# EVB-ANNA-B5_SCHEM_0003_USBhub_FTDI.net
KiCad netlist of a schematic drawn in Altium Designer
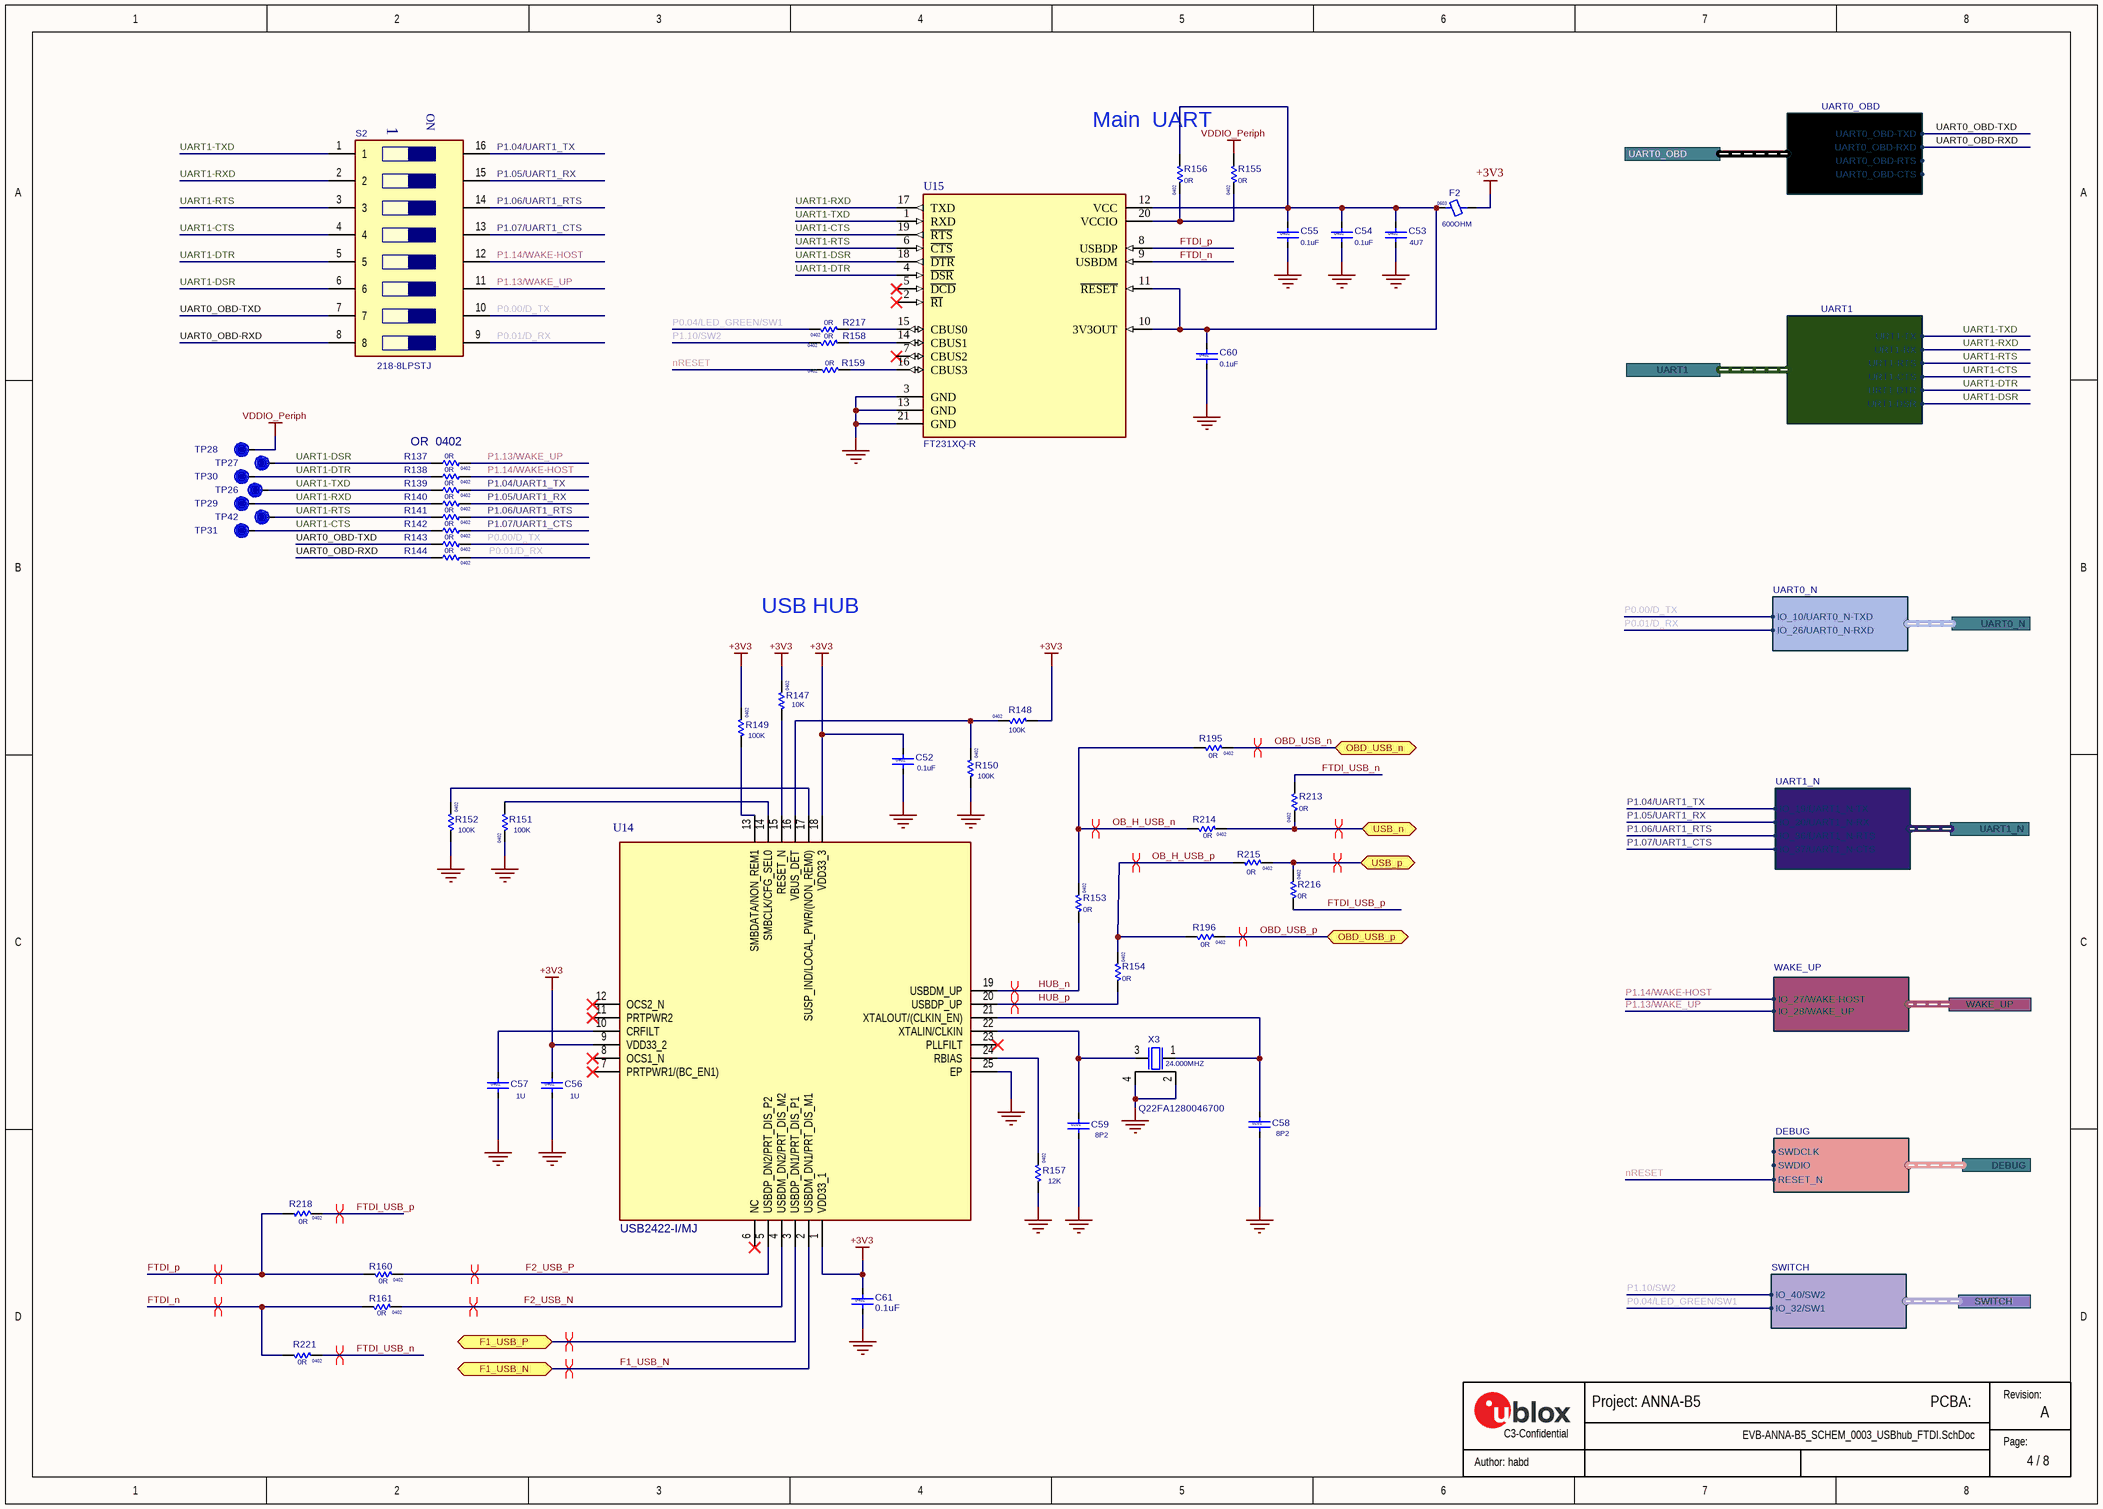
[diagram p0: EVB-ANNA-B5_SCHEM_0003_USBhub_FTDI.SchDoc]

(export (version "E")
  (design (tool "Eeschema 10.0.6"))
  (components
    (comp (ref "C52")
      (value "0.1uF")
      (footprint "Cap 0402 HD")
      (description "Cap, Ceramic 0.1uF 10V 10% X5R 0402")
      (fields
        (field (name "SIZE") "0402")
        (field (name "PART NUMBER") "120-00016")
        (field (name "MANUFACTURER") "Murata Electronics North America")
      )
      (libsource (lib "Arena_Parts_DB_Lib") (part "Cap Chip"))
    )
    (comp (ref "C53")
      (value "4U7")
      (footprint "Cap 0402 HD")
      (description "CAP CER X5R 0402 4U7 20% 10V")
      (fields
        (field (name "SIZE") "0402")
        (field (name "PART NUMBER") "UBXH01-0000243")
        (field (name "TOLERANCE") "20%")
        (field (name "EDITOR") "martin.pilik")
        (field (name "RELEASED BY") "fabrice.bret-dibat")
      )
      (libsource (lib "UBX_Parts_DB_Lib") (part "Cap Chip"))
    )
    (comp (ref "C54")
      (value "0.1uF")
      (footprint "Cap 0402 HD")
      (description "Cap, Ceramic 0.1uF 10V 10% X5R 0402")
      (fields
        (field (name "SIZE") "0402")
        (field (name "PART NUMBER") "120-00016")
        (field (name "MANUFACTURER") "Murata Electronics North America")
      )
      (libsource (lib "Arena_Parts_DB_Lib") (part "Cap Chip"))
    )
    (comp (ref "C55")
      (value "0.1uF")
      (footprint "Cap 0402 HD")
      (description "Cap, Ceramic 0.1uF 10V 10% X5R 0402")
      (fields
        (field (name "SIZE") "0402")
        (field (name "PART NUMBER") "120-00016")
        (field (name "MANUFACTURER") "Murata Electronics North America")
      )
      (libsource (lib "Arena_Parts_DB_Lib") (part "Cap Chip"))
    )
    (comp (ref "C56")
      (value "1U")
      (footprint "Cap 0402 HD")
      (description "CAP CER X5R 0402 1U 10% 10V")
      (fields
        (field (name "SIZE") "0402")
        (field (name "PART NUMBER") "UBXH01-0000248")
        (field (name "TOLERANCE") "10%")
        (field (name "EDITOR") "michael.hein")
        (field (name "RELEASED BY") "igor.shevchenko")
      )
      (libsource (lib "UBX_Parts_DB_Lib") (part "Cap Chip"))
    )
    (comp (ref "C57")
      (value "1U")
      (footprint "Cap 0402 HD")
      (description "CAP CER X5R 0402 1U 10% 10V")
      (fields
        (field (name "SIZE") "0402")
        (field (name "PART NUMBER") "UBXH01-0000248")
        (field (name "TOLERANCE") "10%")
        (field (name "EDITOR") "michael.hein")
        (field (name "RELEASED BY") "igor.shevchenko")
      )
      (libsource (lib "UBX_Parts_DB_Lib") (part "Cap Chip"))
    )
    (comp (ref "C58")
      (value "8P2")
      (footprint "Cap 0201 HD")
      (description "CAP CER C0G 0201 8P2 +/-0.5P 25V")
      (fields
        (field (name "SIZE") "0201")
        (field (name "PART NUMBER") "UBXH01-0013002")
        (field (name "TOLERANCE") "+/-0.5P")
        (field (name "EDITOR") "roland.rust")
        (field (name "RELEASED BY") "roland.rust")
      )
      (libsource (lib "UBX_Parts_DB_Lib") (part "Cap Chip"))
    )
    (comp (ref "C59")
      (value "8P2")
      (footprint "Cap 0201 HD")
      (description "CAP CER C0G 0201 8P2 +/-0.5P 25V")
      (fields
        (field (name "SIZE") "0201")
        (field (name "PART NUMBER") "UBXH01-0013002")
        (field (name "TOLERANCE") "+/-0.5P")
        (field (name "EDITOR") "roland.rust")
        (field (name "RELEASED BY") "roland.rust")
      )
      (libsource (lib "UBX_Parts_DB_Lib") (part "Cap Chip"))
    )
    (comp (ref "C60")
      (value "0.1uF")
      (footprint "Cap 0402 HD")
      (description "Cap, Ceramic 0.1uF 10V 10% X5R 0402")
      (fields
        (field (name "SIZE") "0402")
        (field (name "PART NUMBER") "120-00016")
        (field (name "MANUFACTURER") "Murata Electronics North America")
      )
      (libsource (lib "Arena_Parts_DB_Lib") (part "Cap Chip"))
    )
    (comp (ref "C61")
      (value "0.1uF")
      (footprint "Cap 0402 HD")
      (description "Cap, Ceramic 0.1uF 10V 10% X5R 0402")
      (fields
        (field (name "SIZE") "0402")
        (field (name "PART NUMBER") "120-00016")
        (field (name "MANUFACTURER") "Murata Electronics North America")
      )
      (libsource (lib "Arena_Parts_DB_Lib") (part "Cap Chip"))
    )
    (comp (ref "F2")
      (value "600OHM")
      (footprint "IND_0603_1750Lx950Wx1050H_600x800Pad_800G_FLX")
      (description "FERRITE BEAD 0603 600 OHM AT 100MHZ 600OHM 500mA")
      (fields
        (field (name "SIZE") "0603")
        (field (name "PART NUMBER") "UBXH08-0000001")
        (field (name "MANUFACTURER") "TDK Corporation")
        (field (name "EDITOR") "daniel.hurni")
        (field (name "RELEASED BY") "martin.frauchiger")
      )
      (libsource (lib "UBX_Parts_DB_Lib") (part "FB sm"))
    )
    (comp (ref "R137")
      (value "0R")
      (footprint "RES 0402 HD")
      (description "RES THICK FILM CHIP 0402 0R 0 100mW")
      (fields
        (field (name "SIZE") "0402")
        (field (name "PART NUMBER") "UBXH18-0003002")
        (field (name "TOLERANCE") "0")
        (field (name "EDITOR") "charlotte.biber")
        (field (name "RELEASED BY") "peter.mueller")
      )
      (libsource (lib "UBX_Parts_DB_Lib") (part "Res sm"))
    )
    (comp (ref "R138")
      (value "0R")
      (footprint "RES 0402 HD")
      (description "RES THICK FILM CHIP 0402 0R 0 100mW")
      (fields
        (field (name "SIZE") "0402")
        (field (name "PART NUMBER") "UBXH18-0003002")
        (field (name "TOLERANCE") "0")
        (field (name "EDITOR") "charlotte.biber")
        (field (name "RELEASED BY") "peter.mueller")
      )
      (libsource (lib "UBX_Parts_DB_Lib") (part "Res sm"))
    )
    (comp (ref "R139")
      (value "0R")
      (footprint "RES 0402 HD")
      (description "RES THICK FILM CHIP 0402 0R 0 100mW")
      (fields
        (field (name "SIZE") "0402")
        (field (name "PART NUMBER") "UBXH18-0003002")
        (field (name "TOLERANCE") "0")
        (field (name "EDITOR") "charlotte.biber")
        (field (name "RELEASED BY") "peter.mueller")
      )
      (libsource (lib "UBX_Parts_DB_Lib") (part "Res sm"))
    )
    (comp (ref "R140")
      (value "0R")
      (footprint "RES 0402 HD")
      (description "RES THICK FILM CHIP 0402 0R 0 100mW")
      (fields
        (field (name "SIZE") "0402")
        (field (name "PART NUMBER") "UBXH18-0003002")
        (field (name "TOLERANCE") "0")
        (field (name "EDITOR") "charlotte.biber")
        (field (name "RELEASED BY") "peter.mueller")
      )
      (libsource (lib "UBX_Parts_DB_Lib") (part "Res sm"))
    )
    (comp (ref "R141")
      (value "0R")
      (footprint "RES 0402 HD")
      (description "RES THICK FILM CHIP 0402 0R 0 100mW")
      (fields
        (field (name "SIZE") "0402")
        (field (name "PART NUMBER") "UBXH18-0003002")
        (field (name "TOLERANCE") "0")
        (field (name "EDITOR") "charlotte.biber")
        (field (name "RELEASED BY") "peter.mueller")
      )
      (libsource (lib "UBX_Parts_DB_Lib") (part "Res sm"))
    )
    (comp (ref "R142")
      (value "0R")
      (footprint "RES 0402 HD")
      (description "RES THICK FILM CHIP 0402 0R 0 100mW")
      (fields
        (field (name "SIZE") "0402")
        (field (name "PART NUMBER") "UBXH18-0003002")
        (field (name "TOLERANCE") "0")
        (field (name "EDITOR") "charlotte.biber")
        (field (name "RELEASED BY") "peter.mueller")
      )
      (libsource (lib "UBX_Parts_DB_Lib") (part "Res sm"))
    )
    (comp (ref "R143")
      (value "0R")
      (footprint "RES 0402 HD")
      (description "RES THICK FILM CHIP 0402 0R 0 100mW")
      (fields
        (field (name "SIZE") "0402")
        (field (name "PART NUMBER") "UBXH18-0003002")
        (field (name "TOLERANCE") "0")
        (field (name "EDITOR") "charlotte.biber")
        (field (name "RELEASED BY") "peter.mueller")
      )
      (libsource (lib "UBX_Parts_DB_Lib") (part "Res sm"))
    )
    (comp (ref "R144")
      (value "0R")
      (footprint "RES 0402 HD")
      (description "RES THICK FILM CHIP 0402 0R 0 100mW")
      (fields
        (field (name "SIZE") "0402")
        (field (name "PART NUMBER") "UBXH18-0003002")
        (field (name "TOLERANCE") "0")
        (field (name "EDITOR") "charlotte.biber")
        (field (name "RELEASED BY") "peter.mueller")
      )
      (libsource (lib "UBX_Parts_DB_Lib") (part "Res sm"))
    )
    (comp (ref "R147")
      (value "10K")
      (footprint "RES 0402 HD")
      (description "RES THICK FILM CHIP 0402 10K 1% 63mW")
      (fields
        (field (name "SIZE") "0402")
        (field (name "PART NUMBER") "UBXH18-0000065")
        (field (name "TOLERANCE") "1%")
        (field (name "EDITOR") "erian.bezhani")
        (field (name "RELEASED BY") "massimo.vlacci")
      )
      (libsource (lib "UBX_Parts_DB_Lib") (part "Res sm"))
    )
    (comp (ref "R148")
      (value "100K")
      (footprint "RES 0402 HD")
      (description "RES THICK FILM CHIP 0402 100K 1% 63mW")
      (fields
        (field (name "SIZE") "0402")
        (field (name "PART NUMBER") "UBXH18-0000005")
        (field (name "TOLERANCE") "1%")
        (field (name "EDITOR") "dario.antonaz")
        (field (name "RELEASED BY") "sandro.sestan")
      )
      (libsource (lib "UBX_Parts_DB_Lib") (part "Res sm"))
    )
    (comp (ref "R149")
      (value "100K")
      (footprint "RES 0402 HD")
      (description "RES THICK FILM CHIP 0402 100K 1% 63mW")
      (fields
        (field (name "SIZE") "0402")
        (field (name "PART NUMBER") "UBXH18-0000005")
        (field (name "TOLERANCE") "1%")
        (field (name "EDITOR") "dario.antonaz")
        (field (name "RELEASED BY") "sandro.sestan")
      )
      (libsource (lib "UBX_Parts_DB_Lib") (part "Res sm"))
    )
    (comp (ref "R150")
      (value "100K")
      (footprint "RES 0402 HD")
      (description "RES THICK FILM CHIP 0402 100K 1% 63mW")
      (fields
        (field (name "SIZE") "0402")
        (field (name "PART NUMBER") "UBXH18-0000005")
        (field (name "TOLERANCE") "1%")
        (field (name "EDITOR") "dario.antonaz")
        (field (name "RELEASED BY") "sandro.sestan")
      )
      (libsource (lib "UBX_Parts_DB_Lib") (part "Res sm"))
    )
    (comp (ref "R151")
      (value "100K")
      (footprint "RES 0402 HD")
      (description "RES THICK FILM CHIP 0402 100K 1% 63mW")
      (fields
        (field (name "SIZE") "0402")
        (field (name "PART NUMBER") "UBXH18-0000005")
        (field (name "TOLERANCE") "1%")
        (field (name "EDITOR") "dario.antonaz")
        (field (name "RELEASED BY") "sandro.sestan")
      )
      (libsource (lib "UBX_Parts_DB_Lib") (part "Res sm"))
    )
    (comp (ref "R152")
      (value "100K")
      (footprint "RES 0402 HD")
      (description "RES THICK FILM CHIP 0402 100K 1% 63mW")
      (fields
        (field (name "SIZE") "0402")
        (field (name "PART NUMBER") "UBXH18-0000005")
        (field (name "TOLERANCE") "1%")
        (field (name "EDITOR") "dario.antonaz")
        (field (name "RELEASED BY") "sandro.sestan")
      )
      (libsource (lib "UBX_Parts_DB_Lib") (part "Res sm"))
    )
    (comp (ref "R153")
      (value "0R")
      (footprint "RES 0402 HD")
      (description "RES THICK FILM CHIP 0402 0R 0 100mW")
      (fields
        (field (name "SIZE") "0402")
        (field (name "PART NUMBER") "UBXH18-0003002")
        (field (name "TOLERANCE") "0")
        (field (name "EDITOR") "charlotte.biber")
        (field (name "RELEASED BY") "peter.mueller")
      )
      (libsource (lib "UBX_Parts_DB_Lib") (part "Res sm"))
    )
    (comp (ref "R154")
      (value "0R")
      (footprint "RES 0402 HD")
      (description "RES THICK FILM CHIP 0402 0R 0 100mW")
      (fields
        (field (name "SIZE") "0402")
        (field (name "PART NUMBER") "UBXH18-0003002")
        (field (name "TOLERANCE") "0")
        (field (name "EDITOR") "charlotte.biber")
        (field (name "RELEASED BY") "peter.mueller")
      )
      (libsource (lib "UBX_Parts_DB_Lib") (part "Res sm"))
    )
    (comp (ref "R155")
      (value "0R")
      (footprint "RES 0402 HD")
      (description "RES THICK FILM CHIP 0402 0R 0 100mW")
      (fields
        (field (name "SIZE") "0402")
        (field (name "PART NUMBER") "UBXH18-0003002")
        (field (name "TOLERANCE") "0")
        (field (name "EDITOR") "charlotte.biber")
        (field (name "RELEASED BY") "peter.mueller")
      )
      (libsource (lib "UBX_Parts_DB_Lib") (part "Res sm"))
    )
    (comp (ref "R156")
      (value "0R")
      (footprint "RES 0402 HD")
      (description "RES THICK FILM CHIP 0402 0R 0 100mW")
      (fields
        (field (name "SIZE") "0402")
        (field (name "PART NUMBER") "UBXH18-0003002")
        (field (name "TOLERANCE") "0")
        (field (name "EDITOR") "charlotte.biber")
        (field (name "RELEASED BY") "peter.mueller")
      )
      (libsource (lib "UBX_Parts_DB_Lib") (part "Res sm"))
    )
    (comp (ref "R157")
      (value "12K")
      (footprint "RES_0402_1100Lx600Wx400H_500x600Pad_400G_FLX")
      (description "RES THICK FILM CHIP 0402 12K 1% 62.5mW")
      (fields
        (field (name "SIZE") "0402")
        (field (name "PART NUMBER") "UBXH18-0000133")
        (field (name "TOLERANCE") "1%")
        (field (name "EDITOR") "pierpaolo.arban")
        (field (name "RELEASED BY") "dario.antonaz")
      )
      (libsource (lib "UBX_Parts_DB_Lib") (part "Res sm"))
    )
    (comp (ref "R158")
      (value "0R")
      (footprint "RES_0402_1100Lx600Wx400H_500x600Pad_400G_FLX")
      (description "RES THICK FILM CHIP 0402 0R 0 100mW")
      (fields
        (field (name "SIZE") "0402")
        (field (name "PART NUMBER") "UBXH18-0003002")
        (field (name "TOLERANCE") "0")
        (field (name "EDITOR") "charlotte.biber")
        (field (name "RELEASED BY") "peter.mueller")
      )
      (libsource (lib "UBX_Parts_DB_Lib") (part "Res sm"))
    )
    (comp (ref "R159")
      (value "0R")
      (footprint "RES_0402_1100Lx600Wx400H_500x600Pad_400G_FLX")
      (description "RES THICK FILM CHIP 0402 0R 0 100mW")
      (fields
        (field (name "SIZE") "0402")
        (field (name "PART NUMBER") "UBXH18-0003002")
        (field (name "TOLERANCE") "0")
        (field (name "EDITOR") "charlotte.biber")
        (field (name "RELEASED BY") "peter.mueller")
      )
      (libsource (lib "UBX_Parts_DB_Lib") (part "Res sm"))
    )
    (comp (ref "R160")
      (value "0R")
      (footprint "RES 0402 HD")
      (description "RES THICK FILM CHIP 0402 0R 0 100mW")
      (fields
        (field (name "SIZE") "0402")
        (field (name "PART NUMBER") "UBXH18-0003002")
        (field (name "TOLERANCE") "0")
        (field (name "EDITOR") "charlotte.biber")
        (field (name "RELEASED BY") "peter.mueller")
      )
      (libsource (lib "UBX_Parts_DB_Lib") (part "Res sm"))
    )
    (comp (ref "R161")
      (value "0R")
      (footprint "RES 0402 HD")
      (description "RES THICK FILM CHIP 0402 0R 0 100mW")
      (fields
        (field (name "SIZE") "0402")
        (field (name "PART NUMBER") "UBXH18-0003002")
        (field (name "TOLERANCE") "0")
        (field (name "EDITOR") "charlotte.biber")
        (field (name "RELEASED BY") "peter.mueller")
      )
      (libsource (lib "UBX_Parts_DB_Lib") (part "Res sm"))
    )
    (comp (ref "R195")
      (value "0R")
      (footprint "RES 0402 HD")
      (description "RES THICK FILM CHIP 0402 0R 0 100mW")
      (fields
        (field (name "SIZE") "0402")
        (field (name "PART NUMBER") "UBXH18-0003002")
        (field (name "TOLERANCE") "0")
        (field (name "EDITOR") "charlotte.biber")
        (field (name "RELEASED BY") "peter.mueller")
      )
      (libsource (lib "UBX_Parts_DB_Lib") (part "Res sm"))
    )
    (comp (ref "R196")
      (value "0R")
      (footprint "RES 0402 HD")
      (description "RES THICK FILM CHIP 0402 0R 0 100mW")
      (fields
        (field (name "SIZE") "0402")
        (field (name "PART NUMBER") "UBXH18-0003002")
        (field (name "TOLERANCE") "0")
        (field (name "EDITOR") "charlotte.biber")
        (field (name "RELEASED BY") "peter.mueller")
      )
      (libsource (lib "UBX_Parts_DB_Lib") (part "Res sm"))
    )
    (comp (ref "R213")
      (value "0R")
      (footprint "RES 0402 HD")
      (description "RES THICK FILM CHIP 0402 0R 0 100mW")
      (fields
        (field (name "SIZE") "0402")
        (field (name "PART NUMBER") "UBXH18-0003002")
        (field (name "TOLERANCE") "0")
        (field (name "EDITOR") "charlotte.biber")
        (field (name "RELEASED BY") "peter.mueller")
      )
      (libsource (lib "UBX_Parts_DB_Lib") (part "Res sm"))
    )
    (comp (ref "R214")
      (value "0R")
      (footprint "RES 0402 HD")
      (description "RES THICK FILM CHIP 0402 0R 0 100mW")
      (fields
        (field (name "SIZE") "0402")
        (field (name "PART NUMBER") "UBXH18-0003002")
        (field (name "TOLERANCE") "0")
        (field (name "EDITOR") "charlotte.biber")
        (field (name "RELEASED BY") "peter.mueller")
      )
      (libsource (lib "UBX_Parts_DB_Lib") (part "Res sm"))
    )
    (comp (ref "R215")
      (value "0R")
      (footprint "RES 0402 HD")
      (description "RES THICK FILM CHIP 0402 0R 0 100mW")
      (fields
        (field (name "SIZE") "0402")
        (field (name "PART NUMBER") "UBXH18-0003002")
        (field (name "TOLERANCE") "0")
        (field (name "EDITOR") "charlotte.biber")
        (field (name "RELEASED BY") "peter.mueller")
      )
      (libsource (lib "UBX_Parts_DB_Lib") (part "Res sm"))
    )
    (comp (ref "R216")
      (value "0R")
      (footprint "RES 0402 HD")
      (description "RES THICK FILM CHIP 0402 0R 0 100mW")
      (fields
        (field (name "SIZE") "0402")
        (field (name "PART NUMBER") "UBXH18-0003002")
        (field (name "TOLERANCE") "0")
        (field (name "EDITOR") "charlotte.biber")
        (field (name "RELEASED BY") "peter.mueller")
      )
      (libsource (lib "UBX_Parts_DB_Lib") (part "Res sm"))
    )
    (comp (ref "R217")
      (value "0R")
      (footprint "RES 0402 HD")
      (description "RES THICK FILM CHIP 0402 0R 0 100mW")
      (fields
        (field (name "SIZE") "0402")
        (field (name "PART NUMBER") "UBXH18-0003002")
        (field (name "TOLERANCE") "0")
        (field (name "EDITOR") "charlotte.biber")
        (field (name "RELEASED BY") "peter.mueller")
      )
      (libsource (lib "UBX_Parts_DB_Lib") (part "Res sm"))
    )
    (comp (ref "R218")
      (value "0R")
      (footprint "RES 0402 HD")
      (description "RES THICK FILM CHIP 0402 0R 0 100mW")
      (fields
        (field (name "SIZE") "0402")
        (field (name "PART NUMBER") "UBXH18-0003002")
        (field (name "TOLERANCE") "0")
        (field (name "EDITOR") "charlotte.biber")
        (field (name "RELEASED BY") "peter.mueller")
      )
      (libsource (lib "UBX_Parts_DB_Lib") (part "Res sm"))
    )
    (comp (ref "R221")
      (value "0R")
      (footprint "RES 0402 HD")
      (description "RES THICK FILM CHIP 0402 0R 0 100mW")
      (fields
        (field (name "SIZE") "0402")
        (field (name "PART NUMBER") "UBXH18-0003002")
        (field (name "TOLERANCE") "0")
        (field (name "EDITOR") "charlotte.biber")
        (field (name "RELEASED BY") "peter.mueller")
      )
      (libsource (lib "UBX_Parts_DB_Lib") (part "Res sm"))
    )
    (comp (ref "S2")
      (value "~")
      (footprint "2188LPSTJ")
      (description "Switch")
      (fields
        (field (name "MANUFACTURER_PART_NUMBER") "218-8LPSTJ")
        (field (name "MOUSER PART NUMBER") "774-2188LPSTJ")
        (field (name "ARROW PART NUMBER") "218-8LPSTJ")
      )
      (libsource (lib "SamacSys") (part "218-8LPSTJ"))
    )
    (comp (ref "TP26")
      (value "TP10R")
      (footprint "TP10R")
      (description "Testpoint, Round 1.0mm Dia")
      (fields (field (name "ADDED BY") "Jeremy D") (field (name "CHECKED BY") "Paul B"))
      (libsource (lib "LEGACY_Rigado_AltiumLib") (part "TP_R"))
    )
    (comp (ref "TP27")
      (value "TP10R")
      (footprint "TP10R")
      (description "Testpoint, Round 1.0mm Dia")
      (fields (field (name "ADDED BY") "Jeremy D") (field (name "CHECKED BY") "Paul B"))
      (libsource (lib "LEGACY_Rigado_AltiumLib") (part "TP_R"))
    )
    (comp (ref "TP28")
      (value "TP10R")
      (footprint "TP10R")
      (description "Testpoint, Round 1.0mm Dia")
      (fields (field (name "ADDED BY") "Jeremy D") (field (name "CHECKED BY") "Paul B"))
      (libsource (lib "LEGACY_Rigado_AltiumLib") (part "TP_R"))
    )
    (comp (ref "TP29")
      (value "TP10R")
      (footprint "TP10R")
      (description "Testpoint, Round 1.0mm Dia")
      (fields (field (name "ADDED BY") "Jeremy D") (field (name "CHECKED BY") "Paul B"))
      (libsource (lib "LEGACY_Rigado_AltiumLib") (part "TP_R"))
    )
    (comp (ref "TP30")
      (value "TP10R")
      (footprint "TP10R")
      (description "Testpoint, Round 1.0mm Dia")
      (fields (field (name "ADDED BY") "Jeremy D") (field (name "CHECKED BY") "Paul B"))
      (libsource (lib "LEGACY_Rigado_AltiumLib") (part "TP_R"))
    )
    (comp (ref "TP31")
      (value "TP10R")
      (footprint "TP10R")
      (description "Testpoint, Round 1.0mm Dia")
      (fields (field (name "ADDED BY") "Jeremy D") (field (name "CHECKED BY") "Paul B"))
      (libsource (lib "LEGACY_Rigado_AltiumLib") (part "TP_R"))
    )
    (comp (ref "TP42")
      (value "TP10R")
      (footprint "TP10R")
      (description "Testpoint, Round 1.0mm Dia")
      (fields (field (name "ADDED BY") "Jeremy D") (field (name "CHECKED BY") "Paul B"))
      (libsource (lib "LEGACY_Rigado_AltiumLib") (part "TP_R"))
    )
    (comp (ref "U14")
      (value "~")
      (footprint "SamacSys:QFN50P400X400X100-25N-D")
      (description "Integrated Circuit")
      (fields
        (field (name "MANUFACTURER_PART_NUMBER") "USB2422-I/MJ")
        (field (name "MOUSER PART NUMBER") "579-USB2422-I/MJ")
        (field (name "ARROW PART NUMBER") "USB2422-I/MJ")
      )
      (libsource (lib "*") (part "USB2422-I_MJ"))
    )
    (comp (ref "U15")
      (value "FT231XQ-R")
      (footprint "QFN_5x5_FT231XQ")
      (description "FTDI USB TO SERIAL FULL UART INTERFACE QFN20")
      (fields
        (field (name "PART NUMBER") "UBXH10-0000054")
        (field (name "MANUFACTURER") "FTDI Future Technology Devices International")
        (field (name "EDITOR") "adam.johansson")
      )
      (libsource (lib "UBX_Parts_DB_Lib") (part "FT231XQ-R"))
    )
    (comp (ref "X3")
      (value "24.000MHZ")
      (footprint "XTAL_2016_HD")
      (description "CRYSTAL CL=8PF EPSON 2.0X1.6MM 24.000MHZ 30PPM")
      (fields
        (field (name "PART NUMBER") "UBXH21-0000066")
        (field (name "TOLERANCE") "30PPM")
        (field (name "MANUFACTURER P/N") "Q22FA1280046700")
        (field (name "EDITOR") "adam.johansson")
        (field (name "RELEASED BY") "olof.viklund")
      )
      (libsource (lib "UBX_Parts_DB_Lib") (part "XTAL_4Pin"))
    )
  )
  (nets
    (net (code "8") (name "+3V3") (class "Default")
      (node (ref "C52") (pin "1") (pinfunction "1_1") (pintype "passive"))
      (node (ref "C56") (pin "1") (pinfunction "1_1") (pintype "passive"))
      (node (ref "C61") (pin "1") (pinfunction "1_1") (pintype "passive"))
      (node (ref "F2") (pin "1") (pinfunction "1_1") (pintype "passive"))
      (node (ref "R147") (pin "2") (pinfunction "2_2") (pintype "passive"))
      (node (ref "R148") (pin "2") (pinfunction "2_2") (pintype "passive"))
      (node (ref "R149") (pin "2") (pinfunction "2_2") (pintype "passive"))
      (node (ref "U14") (pin "1") (pinfunction "VDD33_1_1") (pintype "passive"))
      (node (ref "U14") (pin "18") (pinfunction "VDD33_3_18") (pintype "passive"))
      (node (ref "U14") (pin "9") (pinfunction "VDD33_2_9") (pintype "passive"))
    )
    (net (code "9") (name "/F1_USB_N") (class "Default")
      (node (ref "U14") (pin "2") (pinfunction "USBDM_DN1/PRT_DIS_M1_2") (pintype "passive"))
    )
    (net (code "10") (name "/F1_USB_P") (class "Default")
      (node (ref "U14") (pin "3") (pinfunction "USBDP_DN1/PRT_DIS_P1_3") (pintype "passive"))
    )
    (net (code "11") (name "/F2_USB_N") (class "Default")
      (node (ref "R161") (pin "2") (pinfunction "2_2") (pintype "passive"))
      (node (ref "U14") (pin "4") (pinfunction "USBDM_DN2/PRT_DIS_M2_4") (pintype "passive"))
    )
    (net (code "12") (name "/F2_USB_P") (class "Default")
      (node (ref "R160") (pin "2") (pinfunction "2_2") (pintype "passive"))
      (node (ref "U14") (pin "5") (pinfunction "USBDP_DN2/PRT_DIS_P2_5") (pintype "passive"))
    )
    (net (code "13") (name "/FTDI_USB_n") (class "Default")
      (node (ref "R213") (pin "1") (pinfunction "1_1") (pintype "passive"))
      (node (ref "R221") (pin "2") (pinfunction "2_2") (pintype "passive"))
    )
    (net (code "14") (name "/FTDI_USB_p") (class "Default")
      (node (ref "R216") (pin "1") (pinfunction "1_1") (pintype "passive"))
      (node (ref "R218") (pin "1") (pinfunction "1_1") (pintype "passive"))
    )
    (net (code "15") (name "/FTDI_n") (class "Default")
      (node (ref "R161") (pin "1") (pinfunction "1_1") (pintype "passive"))
      (node (ref "R221") (pin "1") (pinfunction "1_1") (pintype "passive"))
      (node (ref "U15") (pin "9") (pinfunction "USBDM_9") (pintype "input"))
    )
    (net (code "16") (name "/FTDI_p") (class "Default")
      (node (ref "R160") (pin "1") (pinfunction "1_1") (pintype "passive"))
      (node (ref "R218") (pin "2") (pinfunction "2_2") (pintype "passive"))
      (node (ref "U15") (pin "8") (pinfunction "USBDP_8") (pintype "input"))
    )
    (net (code "17") (name "/HUB_n") (class "Default")
      (node (ref "R153") (pin "1") (pinfunction "1_1") (pintype "passive"))
      (node (ref "U14") (pin "19") (pinfunction "USBDM_UP_19") (pintype "passive"))
    )
    (net (code "18") (name "/HUB_p") (class "Default")
      (node (ref "R154") (pin "1") (pinfunction "1_1") (pintype "passive"))
      (node (ref "U14") (pin "20") (pinfunction "USBDP_UP_20") (pintype "passive"))
    )
    (net (code "19") (name "/OBD_USB_n") (class "Default")
      (node (ref "R195") (pin "2") (pinfunction "2_2") (pintype "passive"))
    )
    (net (code "20") (name "/OBD_USB_p") (class "Default")
      (node (ref "R196") (pin "2") (pinfunction "2_2") (pintype "passive"))
    )
    (net (code "21") (name "/OB_H_USB_n") (class "Default")
      (node (ref "R153") (pin "2") (pinfunction "2_2") (pintype "passive"))
      (node (ref "R195") (pin "1") (pinfunction "1_1") (pintype "passive"))
      (node (ref "R214") (pin "1") (pinfunction "1_1") (pintype "passive"))
    )
    (net (code "22") (name "/OB_H_USB_p") (class "Default")
      (node (ref "R154") (pin "2") (pinfunction "2_2") (pintype "passive"))
      (node (ref "R196") (pin "1") (pinfunction "1_1") (pintype "passive"))
      (node (ref "R215") (pin "1") (pinfunction "1_1") (pintype "passive"))
    )
    (net (code "23") (name "/P0.00{slash}D_TX") (class "Default")
      (node (ref "R143") (pin "2") (pinfunction "2_2") (pintype "passive"))
      (node (ref "S2") (pin "10") (pintype "passive"))
    )
    (net (code "24") (name "/P0.01{slash}D_RX") (class "Default")
      (node (ref "R144") (pin "2") (pinfunction "2_2") (pintype "passive"))
      (node (ref "S2") (pin "9") (pintype "passive"))
    )
    (net (code "25") (name "/P0.04{slash}LED_GREEN{slash}SW1") (class "Default")
      (node (ref "R217") (pin "1") (pinfunction "1_1") (pintype "passive"))
    )
    (net (code "26") (name "/P1.04{slash}UART1_TX") (class "Default")
      (node (ref "R139") (pin "2") (pinfunction "2_2") (pintype "passive"))
      (node (ref "S2") (pin "16") (pintype "passive"))
    )
    (net (code "27") (name "/P1.05{slash}UART1_RX") (class "Default")
      (node (ref "R140") (pin "2") (pinfunction "2_2") (pintype "passive"))
      (node (ref "S2") (pin "15") (pintype "passive"))
    )
    (net (code "28") (name "/P1.06{slash}UART1_RTS") (class "Default")
      (node (ref "R141") (pin "2") (pinfunction "2_2") (pintype "passive"))
      (node (ref "S2") (pin "14") (pintype "passive"))
    )
    (net (code "29") (name "/P1.07{slash}UART1_CTS") (class "Default")
      (node (ref "R142") (pin "2") (pinfunction "2_2") (pintype "passive"))
      (node (ref "S2") (pin "13") (pintype "passive"))
    )
    (net (code "30") (name "/P1.10{slash}SW2") (class "Default")
      (node (ref "R158") (pin "2") (pinfunction "2_2") (pintype "passive"))
    )
    (net (code "31") (name "/P1.13{slash}WAKE_UP") (class "Default")
      (node (ref "R137") (pin "2") (pinfunction "2_2") (pintype "passive"))
      (node (ref "S2") (pin "11") (pintype "passive"))
    )
    (net (code "32") (name "/P1.14{slash}WAKE-HOST") (class "Default")
      (node (ref "R138") (pin "2") (pinfunction "2_2") (pintype "passive"))
      (node (ref "S2") (pin "12") (pintype "passive"))
    )
    (net (code "33") (name "/UART0_OBD-RXD") (class "Default")
      (node (ref "R144") (pin "1") (pinfunction "1_1") (pintype "passive"))
      (node (ref "S2") (pin "8") (pinfunction "8_8") (pintype "passive"))
    )
    (net (code "34") (name "/UART0_OBD-TXD") (class "Default")
      (node (ref "R143") (pin "1") (pinfunction "1_1") (pintype "passive"))
      (node (ref "S2") (pin "7") (pinfunction "7_7") (pintype "passive"))
    )
    (net (code "35") (name "/UART1-CTS") (class "Default")
      (node (ref "R142") (pin "1") (pinfunction "1_1") (pintype "passive"))
      (node (ref "S2") (pin "4") (pinfunction "4_4") (pintype "passive"))
      (node (ref "TP31") (pin "1") (pintype "passive"))
      (node (ref "U15") (pin "19") (pinfunction "~{RTS}_19") (pintype "output"))
    )
    (net (code "36") (name "/UART1-DSR") (class "Default")
      (node (ref "R137") (pin "1") (pinfunction "1_1") (pintype "passive"))
      (node (ref "S2") (pin "6") (pinfunction "6_6") (pintype "passive"))
      (node (ref "TP27") (pin "1") (pintype "passive"))
      (node (ref "U15") (pin "18") (pinfunction "~{DTR}_18") (pintype "output"))
    )
    (net (code "37") (name "/UART1-DTR") (class "Default")
      (node (ref "R138") (pin "1") (pinfunction "1_1") (pintype "passive"))
      (node (ref "S2") (pin "5") (pinfunction "5_5") (pintype "passive"))
      (node (ref "TP30") (pin "1") (pintype "passive"))
      (node (ref "U15") (pin "4") (pinfunction "~{DSR}_4") (pintype "input"))
    )
    (net (code "38") (name "/UART1-RTS") (class "Default")
      (node (ref "R141") (pin "1") (pinfunction "1_1") (pintype "passive"))
      (node (ref "S2") (pin "3") (pinfunction "3_3") (pintype "passive"))
      (node (ref "TP42") (pin "1") (pintype "passive"))
      (node (ref "U15") (pin "6") (pinfunction "~{CTS}_6") (pintype "input"))
    )
    (net (code "39") (name "/UART1-RXD") (class "Default")
      (node (ref "R140") (pin "1") (pinfunction "1_1") (pintype "passive"))
      (node (ref "S2") (pin "2") (pinfunction "2_2") (pintype "passive"))
      (node (ref "TP29") (pin "1") (pintype "passive"))
      (node (ref "U15") (pin "17") (pinfunction "TXD_17") (pintype "output"))
    )
    (net (code "40") (name "/UART1-TXD") (class "Default")
      (node (ref "R139") (pin "1") (pinfunction "1_1") (pintype "passive"))
      (node (ref "S2") (pin "1") (pinfunction "1_1") (pintype "passive"))
      (node (ref "TP26") (pin "1") (pintype "passive"))
      (node (ref "U15") (pin "1") (pinfunction "RXD_1") (pintype "input"))
    )
    (net (code "41") (name "/USB_n") (class "Default")
      (node (ref "R213") (pin "2") (pinfunction "2_2") (pintype "passive"))
      (node (ref "R214") (pin "2") (pinfunction "2_2") (pintype "passive"))
    )
    (net (code "42") (name "/USB_p") (class "Default")
      (node (ref "R215") (pin "2") (pinfunction "2_2") (pintype "passive"))
      (node (ref "R216") (pin "2") (pinfunction "2_2") (pintype "passive"))
    )
    (net (code "43") (name "/nRESET") (class "Default")
      (node (ref "R159") (pin "2") (pinfunction "2_2") (pintype "passive"))
    )
    (net (code "51") (name "GND") (class "Default")
      (node (ref "C52") (pin "2") (pinfunction "2_2") (pintype "passive"))
      (node (ref "C53") (pin "2") (pinfunction "2_2") (pintype "passive"))
      (node (ref "C54") (pin "2") (pinfunction "2_2") (pintype "passive"))
      (node (ref "C55") (pin "2") (pinfunction "2_2") (pintype "passive"))
      (node (ref "C56") (pin "2") (pinfunction "2_2") (pintype "passive"))
      (node (ref "C57") (pin "2") (pinfunction "2_2") (pintype "passive"))
      (node (ref "C58") (pin "2") (pinfunction "2_2") (pintype "passive"))
      (node (ref "C59") (pin "2") (pinfunction "2_2") (pintype "passive"))
      (node (ref "C60") (pin "2") (pinfunction "2_2") (pintype "passive"))
      (node (ref "C61") (pin "2") (pinfunction "2_2") (pintype "passive"))
      (node (ref "R150") (pin "1") (pinfunction "1_1") (pintype "passive"))
      (node (ref "R151") (pin "2") (pinfunction "2_2") (pintype "passive"))
      (node (ref "R152") (pin "1") (pinfunction "1_1") (pintype "passive"))
      (node (ref "R157") (pin "1") (pinfunction "1_1") (pintype "passive"))
      (node (ref "U14") (pin "25") (pinfunction "EP_25") (pintype "passive"))
      (node (ref "U15") (pin "13") (pinfunction "GND_13") (pintype "power_in"))
      (node (ref "U15") (pin "21") (pinfunction "GND_21") (pintype "power_in"))
      (node (ref "U15") (pin "3") (pinfunction "GND_3") (pintype "power_in"))
      (node (ref "X3") (pin "2") (pintype "passive"))
      (node (ref "X3") (pin "4") (pintype "passive"))
    )
    (net (code "52") (name "Net-(U14-CRFILT)") (class "Default")
      (node (ref "C57") (pin "1") (pinfunction "1_1") (pintype "passive"))
      (node (ref "U14") (pin "10") (pinfunction "CRFILT_10") (pintype "passive"))
    )
    (net (code "53") (name "Net-(U14-RBIAS)") (class "Default")
      (node (ref "R157") (pin "2") (pinfunction "2_2") (pintype "passive"))
      (node (ref "U14") (pin "24") (pinfunction "RBIAS_24") (pintype "passive"))
    )
    (net (code "54") (name "Net-(U14-RESET_N)") (class "Default")
      (node (ref "R147") (pin "1") (pinfunction "1_1") (pintype "passive"))
      (node (ref "U14") (pin "15") (pinfunction "RESET_N_15") (pintype "passive"))
    )
    (net (code "55") (name "Net-(U14-SMBCLK{slash}CFG_SEL0)") (class "Default")
      (node (ref "R151") (pin "1") (pinfunction "1_1") (pintype "passive"))
      (node (ref "U14") (pin "14") (pinfunction "SMBCLK/CFG_SEL0_14") (pintype "passive"))
    )
    (net (code "56") (name "Net-(U14-SMBDATA{slash}NON_REM1)") (class "Default")
      (node (ref "R149") (pin "1") (pinfunction "1_1") (pintype "passive"))
      (node (ref "U14") (pin "13") (pinfunction "SMBDATA/NON_REM1_13") (pintype "passive"))
    )
    (net (code "57") (name "Net-(U14-SUSP_IND{slash}LOCAL_PWR{slash}(NON_REM0))") (class "Default")
      (node (ref "R152") (pin "2") (pinfunction "2_2") (pintype "passive"))
      (node (ref "U14") (pin "17") (pinfunction "SUSP_IND/LOCAL_PWR/(NON_REM0)_17") (pintype "passive"))
    )
    (net (code "58") (name "Net-(U14-VBUS_DET)") (class "Default")
      (node (ref "R148") (pin "1") (pinfunction "1_1") (pintype "passive"))
      (node (ref "R150") (pin "2") (pinfunction "2_2") (pintype "passive"))
      (node (ref "U14") (pin "16") (pinfunction "VBUS_DET_16") (pintype "passive"))
    )
    (net (code "59") (name "Net-(U14-XTALIN{slash}CLKIN)") (class "Default")
      (node (ref "C59") (pin "1") (pinfunction "1_1") (pintype "passive"))
      (node (ref "U14") (pin "22") (pinfunction "XTALIN/CLKIN_22") (pintype "passive"))
      (node (ref "X3") (pin "3") (pintype "passive"))
    )
    (net (code "60") (name "Net-(U14-XTALOUT{slash}(CLKIN_EN))") (class "Default")
      (node (ref "C58") (pin "1") (pinfunction "1_1") (pintype "passive"))
      (node (ref "U14") (pin "21") (pinfunction "XTALOUT/(CLKIN_EN)_21") (pintype "passive"))
      (node (ref "X3") (pin "1") (pintype "passive"))
    )
    (net (code "61") (name "Net-(U15-3V3OUT)") (class "Default")
      (node (ref "C53") (pin "1") (pinfunction "1_1") (pintype "passive"))
      (node (ref "C54") (pin "1") (pinfunction "1_1") (pintype "passive"))
      (node (ref "C55") (pin "1") (pinfunction "1_1") (pintype "passive"))
      (node (ref "C60") (pin "1") (pinfunction "1_1") (pintype "passive"))
      (node (ref "F2") (pin "2") (pinfunction "2_2") (pintype "passive"))
      (node (ref "R156") (pin "1") (pinfunction "1_1") (pintype "passive"))
      (node (ref "U15") (pin "10") (pinfunction "3V3OUT_10") (pintype "input"))
      (node (ref "U15") (pin "11") (pinfunction "~{RESET}_11") (pintype "input"))
      (node (ref "U15") (pin "12") (pinfunction "VCC_12") (pintype "power_in"))
    )
    (net (code "62") (name "Net-(U15-CBUS0)") (class "Default")
      (node (ref "R217") (pin "2") (pinfunction "2_2") (pintype "passive"))
      (node (ref "U15") (pin "15") (pinfunction "CBUS0_15") (pintype "bidirectional"))
    )
    (net (code "63") (name "Net-(U15-CBUS1)") (class "Default")
      (node (ref "R158") (pin "1") (pinfunction "1_1") (pintype "passive"))
      (node (ref "U15") (pin "14") (pinfunction "CBUS1_14") (pintype "bidirectional"))
    )
    (net (code "64") (name "Net-(U15-CBUS3)") (class "Default")
      (node (ref "R159") (pin "1") (pinfunction "1_1") (pintype "passive"))
      (node (ref "U15") (pin "16") (pinfunction "CBUS3_16") (pintype "bidirectional"))
    )
    (net (code "65") (name "Net-(U15-VCCIO)") (class "Default")
      (node (ref "R155") (pin "2") (pinfunction "2_2") (pintype "passive"))
      (node (ref "R156") (pin "2") (pinfunction "2_2") (pintype "passive"))
      (node (ref "U15") (pin "20") (pinfunction "VCCIO_20") (pintype "power_in"))
    )
    (net (code "66") (name "VDDIO_Periph") (class "Default")
      (node (ref "R155") (pin "1") (pinfunction "1_1") (pintype "passive"))
      (node (ref "TP28") (pin "1") (pintype "passive"))
    )
    (net (code "67") (name "unconnected-(U14-NC-Pad6)") (class "Default")
      (node (ref "U14") (pin "6") (pinfunction "NC_6") (pintype "passive+no_connect"))
    )
    (net (code "68") (name "unconnected-(U14-OCS1_N-Pad8)") (class "Default")
      (node (ref "U14") (pin "8") (pinfunction "OCS1_N_8") (pintype "passive+no_connect"))
    )
    (net (code "69") (name "unconnected-(U14-OCS2_N-Pad12)") (class "Default")
      (node (ref "U14") (pin "12") (pinfunction "OCS2_N_12") (pintype "passive+no_connect"))
    )
    (net (code "70") (name "unconnected-(U14-PLLFILT-Pad23)") (class "Default")
      (node (ref "U14") (pin "23") (pinfunction "PLLFILT_23") (pintype "passive+no_connect"))
    )
    (net (code "71") (name "unconnected-(U14-PRTPWR1{slash}(BC_EN1)-Pad7)") (class "Default")
      (node (ref "U14") (pin "7") (pinfunction "PRTPWR1/(BC_EN1)_7") (pintype "passive+no_connect"))
    )
    (net (code "72") (name "unconnected-(U14-PRTPWR2-Pad11)") (class "Default")
      (node (ref "U14") (pin "11") (pinfunction "PRTPWR2_11") (pintype "passive+no_connect"))
    )
    (net (code "73") (name "unconnected-(U15-CBUS2-Pad7)") (class "Default")
      (node (ref "U15") (pin "7") (pinfunction "CBUS2_7") (pintype "bidirectional+no_connect"))
    )
    (net (code "74") (name "unconnected-(U15-~{DCD}-Pad5)") (class "Default")
      (node (ref "U15") (pin "5") (pinfunction "~{DCD}_5") (pintype "input+no_connect"))
    )
    (net (code "75") (name "unconnected-(U15-~{RI}-Pad2)") (class "Default")
      (node (ref "U15") (pin "2") (pinfunction "~{RI}_2") (pintype "input+no_connect"))
    )
  )
)
